# MD.net
KiCad netlist of a schematic drawn in EAGLE
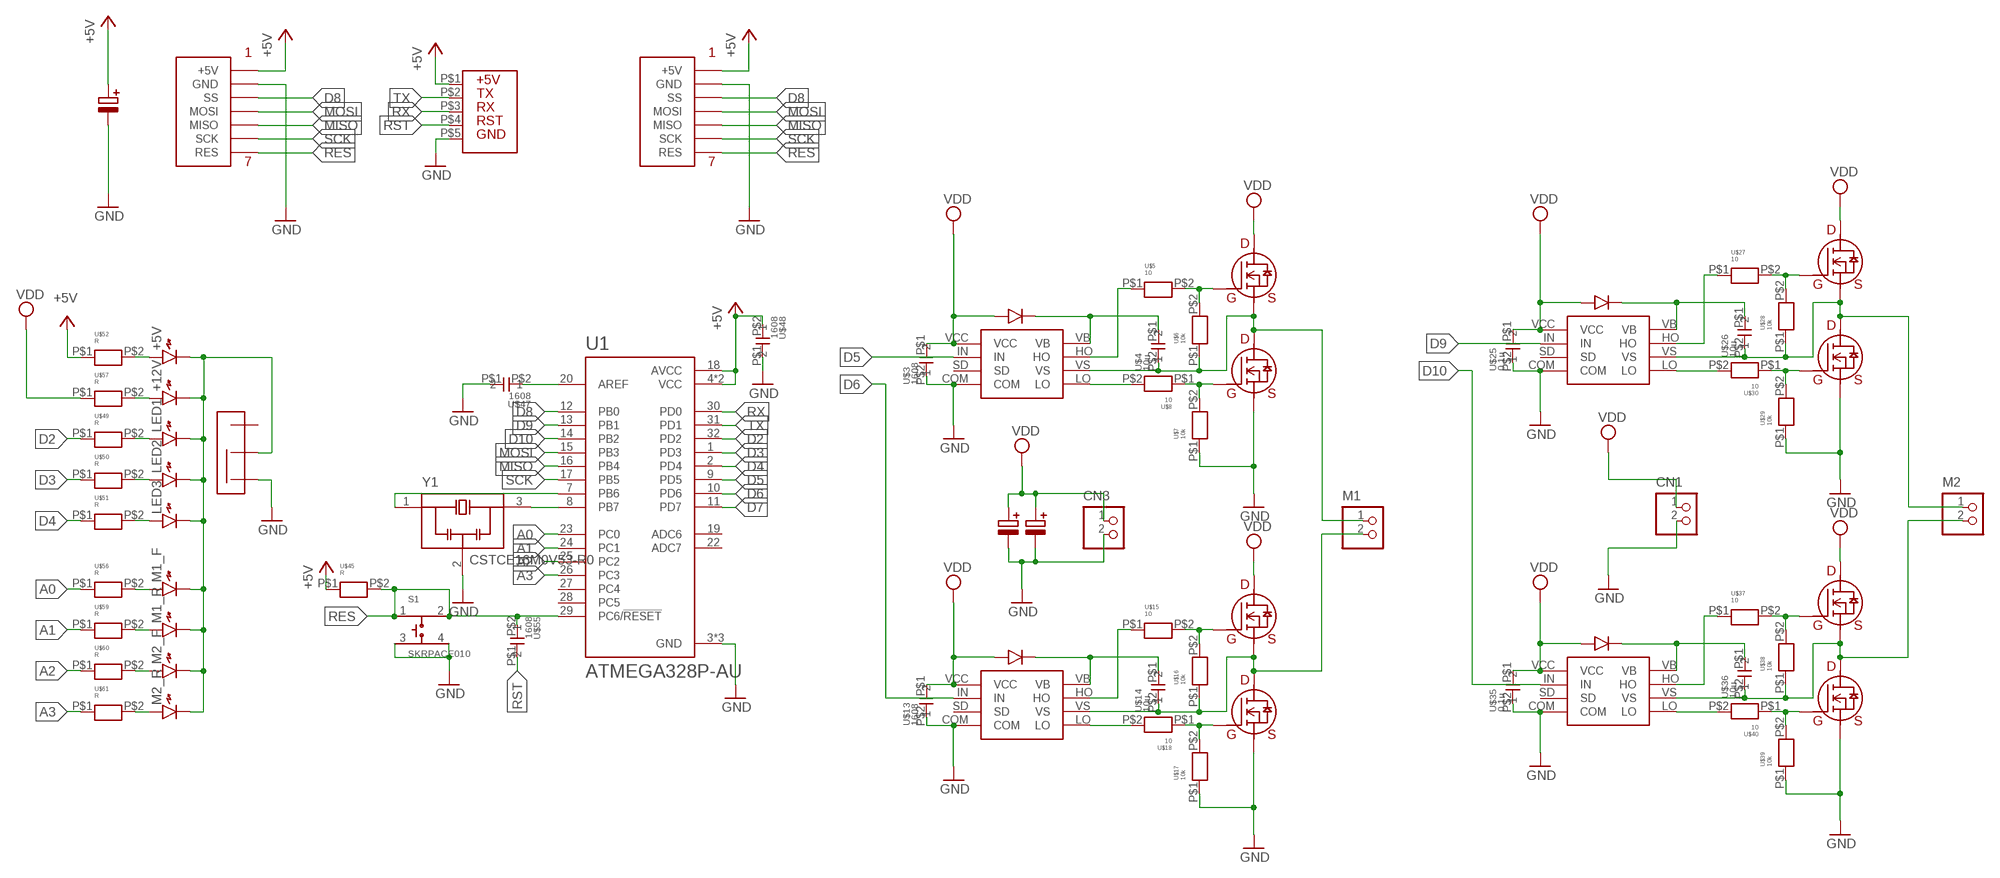
[diagram p0: schematic, sheet 1]

(export (version "E")
  (design (tool "Eeschema 10.0.6"))
  (components
    (comp (ref "+5V")
      (value "LED1608")
      (footprint "eagle-import:LED1608")
      (libsource (lib "eagle-import") (part "LED1608"))
    )
    (comp (ref "+12V")
      (value "LED1608")
      (footprint "eagle-import:LED1608")
      (libsource (lib "eagle-import") (part "LED1608"))
    )
    (comp (ref "CN1")
      (value "B2B-XH-A")
      (footprint "eagle-import:B2B-XH-A")
      (libsource (lib "eagle-import") (part "B2B-XH-A"))
    )
    (comp (ref "CN3")
      (value "B2B-XH-A")
      (footprint "eagle-import:B2B-XH-A")
      (libsource (lib "eagle-import") (part "B2B-XH-A"))
    )
    (comp (ref "LED1")
      (value "LED1608")
      (footprint "eagle-import:LED1608")
      (libsource (lib "eagle-import") (part "LED1608"))
    )
    (comp (ref "LED2")
      (value "LED1608")
      (footprint "eagle-import:LED1608")
      (libsource (lib "eagle-import") (part "LED1608"))
    )
    (comp (ref "LED3")
      (value "LED1608")
      (footprint "eagle-import:LED1608")
      (libsource (lib "eagle-import") (part "LED1608"))
    )
    (comp (ref "M1")
      (value "S2B-XH-A")
      (footprint "eagle-import:S2B-XH-A")
      (libsource (lib "eagle-import") (part "S2B-XH-A"))
    )
    (comp (ref "M1_F")
      (value "LED1608")
      (footprint "eagle-import:LED1608")
      (libsource (lib "eagle-import") (part "LED1608"))
    )
    (comp (ref "M1_R")
      (value "LED1608")
      (footprint "eagle-import:LED1608")
      (libsource (lib "eagle-import") (part "LED1608"))
    )
    (comp (ref "M2")
      (value "S2B-XH-A")
      (footprint "eagle-import:S2B-XH-A")
      (libsource (lib "eagle-import") (part "S2B-XH-A"))
    )
    (comp (ref "M2_F")
      (value "LED1608")
      (footprint "eagle-import:LED1608")
      (libsource (lib "eagle-import") (part "LED1608"))
    )
    (comp (ref "M2_R")
      (value "LED1608")
      (footprint "eagle-import:LED1608")
      (libsource (lib "eagle-import") (part "LED1608"))
    )
    (comp (ref "S1")
      (value "SKRPACE010")
      (footprint "eagle-import:SW_SKRPACE010")
      (fields (field (name "MF") "ALPS"))
      (libsource (lib "eagle-import") (part "SKRPACE010"))
    )
    (comp (ref "U$1")
      (value "IR2302")
      (footprint "eagle-import:IR2302")
      (libsource (lib "eagle-import") (part "IR2302"))
    )
    (comp (ref "U$2")
      (value "1N4148")
      (footprint "eagle-import:1N4148")
      (libsource (lib "eagle-import") (part "1N4148"))
    )
    (comp (ref "U$3")
      (value "1608")
      (footprint "eagle-import:CON")
      (libsource (lib "eagle-import") (part "1608"))
    )
    (comp (ref "U$4")
      (value "10u")
      (footprint "eagle-import:CON")
      (libsource (lib "eagle-import") (part "1608"))
    )
    (comp (ref "U$5")
      (value "10")
      (footprint "eagle-import:1608")
      (libsource (lib "eagle-import") (part "R"))
    )
    (comp (ref "U$6")
      (value "10k")
      (footprint "eagle-import:1608")
      (libsource (lib "eagle-import") (part "R"))
    )
    (comp (ref "U$7")
      (value "10k")
      (footprint "eagle-import:1608")
      (libsource (lib "eagle-import") (part "R"))
    )
    (comp (ref "U$8")
      (value "10")
      (footprint "eagle-import:1608")
      (libsource (lib "eagle-import") (part "R"))
    )
    (comp (ref "U$9")
      (value "TK8S06K3L")
      (footprint "eagle-import:TK8S06K3L")
      (libsource (lib "eagle-import") (part "TK8S06K3L"))
    )
    (comp (ref "U$10")
      (value "TK8S06K3L")
      (footprint "eagle-import:TK8S06K3L")
      (libsource (lib "eagle-import") (part "TK8S06K3L"))
    )
    (comp (ref "U$11")
      (value "IR2302")
      (footprint "eagle-import:IR2302")
      (libsource (lib "eagle-import") (part "IR2302"))
    )
    (comp (ref "U$12")
      (value "1N4148")
      (footprint "eagle-import:1N4148")
      (libsource (lib "eagle-import") (part "1N4148"))
    )
    (comp (ref "U$13")
      (value "1608")
      (footprint "eagle-import:CON")
      (libsource (lib "eagle-import") (part "1608"))
    )
    (comp (ref "U$14")
      (value "10u")
      (footprint "eagle-import:CON")
      (libsource (lib "eagle-import") (part "1608"))
    )
    (comp (ref "U$15")
      (value "10")
      (footprint "eagle-import:1608")
      (libsource (lib "eagle-import") (part "R"))
    )
    (comp (ref "U$16")
      (value "10k")
      (footprint "eagle-import:1608")
      (libsource (lib "eagle-import") (part "R"))
    )
    (comp (ref "U$17")
      (value "10k")
      (footprint "eagle-import:1608")
      (libsource (lib "eagle-import") (part "R"))
    )
    (comp (ref "U$18")
      (value "10")
      (footprint "eagle-import:1608")
      (libsource (lib "eagle-import") (part "R"))
    )
    (comp (ref "U$19")
      (value "TK8S06K3L")
      (footprint "eagle-import:TK8S06K3L")
      (libsource (lib "eagle-import") (part "TK8S06K3L"))
    )
    (comp (ref "U$20")
      (value "TK8S06K3L")
      (footprint "eagle-import:TK8S06K3L")
      (libsource (lib "eagle-import") (part "TK8S06K3L"))
    )
    (comp (ref "U$21")
      (value "25V100")
      (footprint "eagle-import:25V100")
      (libsource (lib "eagle-import") (part "25V100"))
    )
    (comp (ref "U$22")
      (value "25V100")
      (footprint "eagle-import:25V100")
      (libsource (lib "eagle-import") (part "25V100"))
    )
    (comp (ref "U$23")
      (value "IR2302")
      (footprint "eagle-import:IR2302")
      (libsource (lib "eagle-import") (part "IR2302"))
    )
    (comp (ref "U$24")
      (value "1N4148")
      (footprint "eagle-import:1N4148")
      (libsource (lib "eagle-import") (part "1N4148"))
    )
    (comp (ref "U$25")
      (value "0.1u")
      (footprint "eagle-import:CON")
      (libsource (lib "eagle-import") (part "1608"))
    )
    (comp (ref "U$26")
      (value "10u")
      (footprint "eagle-import:CON")
      (libsource (lib "eagle-import") (part "1608"))
    )
    (comp (ref "U$27")
      (value "10")
      (footprint "eagle-import:1608")
      (libsource (lib "eagle-import") (part "R"))
    )
    (comp (ref "U$28")
      (value "10k")
      (footprint "eagle-import:1608")
      (libsource (lib "eagle-import") (part "R"))
    )
    (comp (ref "U$29")
      (value "10k")
      (footprint "eagle-import:1608")
      (libsource (lib "eagle-import") (part "R"))
    )
    (comp (ref "U$30")
      (value "10")
      (footprint "eagle-import:1608")
      (libsource (lib "eagle-import") (part "R"))
    )
    (comp (ref "U$31")
      (value "TK8S06K3L")
      (footprint "eagle-import:TK8S06K3L")
      (libsource (lib "eagle-import") (part "TK8S06K3L"))
    )
    (comp (ref "U$32")
      (value "TK8S06K3L")
      (footprint "eagle-import:TK8S06K3L")
      (libsource (lib "eagle-import") (part "TK8S06K3L"))
    )
    (comp (ref "U$33")
      (value "IR2302")
      (footprint "eagle-import:IR2302")
      (libsource (lib "eagle-import") (part "IR2302"))
    )
    (comp (ref "U$34")
      (value "1N4148")
      (footprint "eagle-import:1N4148")
      (libsource (lib "eagle-import") (part "1N4148"))
    )
    (comp (ref "U$35")
      (value "0.1u")
      (footprint "eagle-import:CON")
      (libsource (lib "eagle-import") (part "1608"))
    )
    (comp (ref "U$36")
      (value "10u")
      (footprint "eagle-import:CON")
      (libsource (lib "eagle-import") (part "1608"))
    )
    (comp (ref "U$37")
      (value "10")
      (footprint "eagle-import:1608")
      (libsource (lib "eagle-import") (part "R"))
    )
    (comp (ref "U$38")
      (value "10k")
      (footprint "eagle-import:1608")
      (libsource (lib "eagle-import") (part "R"))
    )
    (comp (ref "U$39")
      (value "10k")
      (footprint "eagle-import:1608")
      (libsource (lib "eagle-import") (part "R"))
    )
    (comp (ref "U$40")
      (value "10")
      (footprint "eagle-import:1608")
      (libsource (lib "eagle-import") (part "R"))
    )
    (comp (ref "U$41")
      (value "TK8S06K3L")
      (footprint "eagle-import:TK8S06K3L")
      (libsource (lib "eagle-import") (part "TK8S06K3L"))
    )
    (comp (ref "U$42")
      (value "TK8S06K3L")
      (footprint "eagle-import:TK8S06K3L")
      (libsource (lib "eagle-import") (part "TK8S06K3L"))
    )
    (comp (ref "U$45")
      (value "R")
      (footprint "eagle-import:1608")
      (libsource (lib "eagle-import") (part "R"))
    )
    (comp (ref "U$46")
      (value "SPI")
      (footprint "eagle-import:SPI")
      (libsource (lib "eagle-import") (part "SPI"))
    )
    (comp (ref "U$47")
      (value "1608")
      (footprint "eagle-import:CON")
      (libsource (lib "eagle-import") (part "1608"))
    )
    (comp (ref "U$48")
      (value "1608")
      (footprint "eagle-import:CON")
      (libsource (lib "eagle-import") (part "1608"))
    )
    (comp (ref "U$49")
      (value "R")
      (footprint "eagle-import:1608")
      (libsource (lib "eagle-import") (part "R"))
    )
    (comp (ref "U$50")
      (value "R")
      (footprint "eagle-import:1608")
      (libsource (lib "eagle-import") (part "R"))
    )
    (comp (ref "U$51")
      (value "R")
      (footprint "eagle-import:1608")
      (libsource (lib "eagle-import") (part "R"))
    )
    (comp (ref "U$52")
      (value "R")
      (footprint "eagle-import:1608")
      (libsource (lib "eagle-import") (part "R"))
    )
    (comp (ref "U$53")
      (value "SSW")
      (footprint "eagle-import:SSW")
      (libsource (lib "eagle-import") (part "SSW"))
    )
    (comp (ref "U$54")
      (value "SI")
      (footprint "eagle-import:SI")
      (libsource (lib "eagle-import") (part "SI"))
    )
    (comp (ref "U$55")
      (value "1608")
      (footprint "eagle-import:CON")
      (libsource (lib "eagle-import") (part "1608"))
    )
    (comp (ref "U$56")
      (value "R")
      (footprint "eagle-import:1608")
      (libsource (lib "eagle-import") (part "R"))
    )
    (comp (ref "U$57")
      (value "R")
      (footprint "eagle-import:1608")
      (libsource (lib "eagle-import") (part "R"))
    )
    (comp (ref "U$58")
      (value "25V100")
      (footprint "eagle-import:25V100")
      (libsource (lib "eagle-import") (part "25V100"))
    )
    (comp (ref "U$59")
      (value "R")
      (footprint "eagle-import:1608")
      (libsource (lib "eagle-import") (part "R"))
    )
    (comp (ref "U$60")
      (value "R")
      (footprint "eagle-import:1608")
      (libsource (lib "eagle-import") (part "R"))
    )
    (comp (ref "U$61")
      (value "R")
      (footprint "eagle-import:1608")
      (libsource (lib "eagle-import") (part "R"))
    )
    (comp (ref "U$62")
      (value "SPI")
      (footprint "eagle-import:SPI")
      (libsource (lib "eagle-import") (part "SPI"))
    )
    (comp (ref "U1")
      (value "ATMEGA328P-AU")
      (footprint "eagle-import:QFP80P900X900X120-32N")
      (fields (field (name "MF") "Microchip Technology"))
      (libsource (lib "eagle-import") (part "ATMEGA328P-AU"))
    )
    (comp (ref "Y1")
      (value "CSTCE16M0V53-R0")
      (footprint "eagle-import:OSC_CSTCE16M0V53-R0")
      (fields (field (name "MANUFACTURER") "Murata"))
      (libsource (lib "eagle-import") (part "CSTCE16M0V53-R0"))
    )
  )
  (nets
    (net (code "1") (name "+5V") (class "Default")
      (node (ref "U$45") (pin "P$1") (pinfunction "P$1_P$1") (pintype "bidirectional"))
      (node (ref "U$46") (pin "P$1") (pinfunction "+5V_P$1") (pintype "bidirectional"))
      (node (ref "U$48") (pin "P$2") (pinfunction "2_P$2") (pintype "bidirectional"))
      (node (ref "U$52") (pin "P$1") (pinfunction "P$1_P$1") (pintype "bidirectional"))
      (node (ref "U$54") (pin "P$1") (pinfunction "P$1_P$1") (pintype "bidirectional"))
      (node (ref "U$58") (pin "P$1") (pinfunction "P$1_P$1") (pintype "bidirectional"))
      (node (ref "U$62") (pin "P$1") (pinfunction "+5V_P$1") (pintype "bidirectional"))
      (node (ref "U1") (pin "18") (pinfunction "AVCC_18") (pintype "power_in"))
      (node (ref "U1") (pin "4") (pinfunction "VCC_4") (pintype "power_in"))
      (node (ref "U1") (pin "6") (pinfunction "VCC_6") (pintype "power_in"))
    )
    (net (code "2") (name "A0") (class "Default")
      (node (ref "U$56") (pin "P$1") (pinfunction "P$1_P$1") (pintype "bidirectional"))
      (node (ref "U1") (pin "23") (pinfunction "PC0_23") (pintype "bidirectional"))
    )
    (net (code "3") (name "A1") (class "Default")
      (node (ref "U$59") (pin "P$1") (pinfunction "P$1_P$1") (pintype "bidirectional"))
      (node (ref "U1") (pin "24") (pinfunction "PC1_24") (pintype "bidirectional"))
    )
    (net (code "4") (name "A2") (class "Default")
      (node (ref "U$60") (pin "P$1") (pinfunction "P$1_P$1") (pintype "bidirectional"))
      (node (ref "U1") (pin "25") (pinfunction "PC2_25") (pintype "bidirectional"))
    )
    (net (code "5") (name "A3") (class "Default")
      (node (ref "U$61") (pin "P$1") (pinfunction "P$1_P$1") (pintype "bidirectional"))
      (node (ref "U1") (pin "26") (pinfunction "PC3_26") (pintype "bidirectional"))
    )
    (net (code "6") (name "D2") (class "Default")
      (node (ref "U$49") (pin "P$1") (pinfunction "P$1_P$1") (pintype "bidirectional"))
      (node (ref "U1") (pin "32") (pinfunction "PD2_32") (pintype "bidirectional"))
    )
    (net (code "7") (name "D3") (class "Default")
      (node (ref "U$50") (pin "P$1") (pinfunction "P$1_P$1") (pintype "bidirectional"))
      (node (ref "U1") (pin "1") (pinfunction "PD3_1") (pintype "bidirectional"))
    )
    (net (code "8") (name "D4") (class "Default")
      (node (ref "U$51") (pin "P$1") (pinfunction "P$1_P$1") (pintype "bidirectional"))
      (node (ref "U1") (pin "2") (pinfunction "PD4_2") (pintype "bidirectional"))
    )
    (net (code "9") (name "D5") (class "Default")
      (node (ref "U$1") (pin "IN") (pinfunction "IN_IN") (pintype "bidirectional"))
      (node (ref "U1") (pin "9") (pinfunction "PD5_9") (pintype "bidirectional"))
    )
    (net (code "10") (name "D6") (class "Default")
      (node (ref "U$11") (pin "IN") (pinfunction "IN_IN") (pintype "bidirectional"))
      (node (ref "U1") (pin "10") (pinfunction "PD6_10") (pintype "bidirectional"))
    )
    (net (code "11") (name "D7") (class "Default")
      (node (ref "U1") (pin "11") (pinfunction "PD7_11") (pintype "bidirectional"))
    )
    (net (code "12") (name "D8") (class "Default")
      (node (ref "U$46") (pin "P$3") (pinfunction "SS_P$3") (pintype "bidirectional"))
      (node (ref "U$62") (pin "P$3") (pinfunction "SS_P$3") (pintype "bidirectional"))
      (node (ref "U1") (pin "12") (pinfunction "PB0_12") (pintype "bidirectional"))
    )
    (net (code "13") (name "D9") (class "Default")
      (node (ref "U$23") (pin "IN") (pinfunction "IN_IN") (pintype "bidirectional"))
      (node (ref "U1") (pin "13") (pinfunction "PB1_13") (pintype "bidirectional"))
    )
    (net (code "14") (name "D10") (class "Default")
      (node (ref "U$33") (pin "IN") (pinfunction "IN_IN") (pintype "bidirectional"))
      (node (ref "U1") (pin "14") (pinfunction "PB2_14") (pintype "bidirectional"))
    )
    (net (code "15") (name "GND") (class "Default")
      (node (ref "CN1") (pin "2") (pinfunction "2_2") (pintype "passive"))
      (node (ref "CN3") (pin "2") (pinfunction "2_2") (pintype "passive"))
      (node (ref "S1") (pin "3") (pinfunction "3_3") (pintype "bidirectional"))
      (node (ref "S1") (pin "4") (pinfunction "4_4") (pintype "bidirectional"))
      (node (ref "U$1") (pin "COM") (pinfunction "COM_COM") (pintype "bidirectional"))
      (node (ref "U$10") (pin "S") (pinfunction "S_S") (pintype "bidirectional"))
      (node (ref "U$11") (pin "COM") (pinfunction "COM_COM") (pintype "bidirectional"))
      (node (ref "U$13") (pin "P$2") (pinfunction "2_P$2") (pintype "bidirectional"))
      (node (ref "U$17") (pin "P$1") (pinfunction "P$1_P$1") (pintype "bidirectional"))
      (node (ref "U$20") (pin "S") (pinfunction "S_S") (pintype "bidirectional"))
      (node (ref "U$21") (pin "P$2") (pinfunction "P$2_P$2") (pintype "bidirectional"))
      (node (ref "U$22") (pin "P$2") (pinfunction "P$2_P$2") (pintype "bidirectional"))
      (node (ref "U$23") (pin "COM") (pinfunction "COM_COM") (pintype "bidirectional"))
      (node (ref "U$25") (pin "P$2") (pinfunction "2_P$2") (pintype "bidirectional"))
      (node (ref "U$29") (pin "P$1") (pinfunction "P$1_P$1") (pintype "bidirectional"))
      (node (ref "U$3") (pin "P$2") (pinfunction "2_P$2") (pintype "bidirectional"))
      (node (ref "U$32") (pin "S") (pinfunction "S_S") (pintype "bidirectional"))
      (node (ref "U$33") (pin "COM") (pinfunction "COM_COM") (pintype "bidirectional"))
      (node (ref "U$35") (pin "P$2") (pinfunction "2_P$2") (pintype "bidirectional"))
      (node (ref "U$39") (pin "P$1") (pinfunction "P$1_P$1") (pintype "bidirectional"))
      (node (ref "U$42") (pin "S") (pinfunction "S_S") (pintype "bidirectional"))
      (node (ref "U$46") (pin "P$2") (pinfunction "GND_P$2") (pintype "bidirectional"))
      (node (ref "U$47") (pin "P$1") (pinfunction "1_P$1") (pintype "bidirectional"))
      (node (ref "U$48") (pin "P$1") (pinfunction "1_P$1") (pintype "bidirectional"))
      (node (ref "U$53") (pin "P$1") (pinfunction "P$1_P$1") (pintype "bidirectional"))
      (node (ref "U$54") (pin "P$5") (pinfunction "P$5_P$5") (pintype "bidirectional"))
      (node (ref "U$58") (pin "P$2") (pinfunction "P$2_P$2") (pintype "bidirectional"))
      (node (ref "U$62") (pin "P$2") (pinfunction "GND_P$2") (pintype "bidirectional"))
      (node (ref "U$7") (pin "P$1") (pinfunction "P$1_P$1") (pintype "bidirectional"))
      (node (ref "U1") (pin "21") (pinfunction "GND_21") (pintype "power_in"))
      (node (ref "U1") (pin "3") (pinfunction "GND_3") (pintype "power_in"))
      (node (ref "U1") (pin "5") (pinfunction "GND_5") (pintype "power_in"))
      (node (ref "Y1") (pin "2") (pinfunction "GND_2") (pintype "power_in"))
    )
    (net (code "16") (name "MISO") (class "Default")
      (node (ref "U$46") (pin "P$5") (pinfunction "MISO_P$5") (pintype "bidirectional"))
      (node (ref "U$62") (pin "P$5") (pinfunction "MISO_P$5") (pintype "bidirectional"))
      (node (ref "U1") (pin "16") (pinfunction "PB4_16") (pintype "bidirectional"))
    )
    (net (code "17") (name "MOSI") (class "Default")
      (node (ref "U$46") (pin "P$4") (pinfunction "MOSI_P$4") (pintype "bidirectional"))
      (node (ref "U$62") (pin "P$4") (pinfunction "MOSI_P$4") (pintype "bidirectional"))
      (node (ref "U1") (pin "15") (pinfunction "PB3_15") (pintype "bidirectional"))
    )
    (net (code "18") (name "Net-(+5V-PadA)") (class "Default")
      (node (ref "+5V") (pin "A") (pinfunction "A_A") (pintype "passive"))
      (node (ref "U$52") (pin "P$2") (pinfunction "P$2_P$2") (pintype "bidirectional"))
    )
    (net (code "19") (name "Net-(+12V-PadA)") (class "Default")
      (node (ref "+12V") (pin "A") (pinfunction "A_A") (pintype "passive"))
      (node (ref "U$57") (pin "P$2") (pinfunction "P$2_P$2") (pintype "bidirectional"))
    )
    (net (code "20") (name "Net-(LED1-PadA)") (class "Default")
      (node (ref "LED1") (pin "A") (pinfunction "A_A") (pintype "passive"))
      (node (ref "U$49") (pin "P$2") (pinfunction "P$2_P$2") (pintype "bidirectional"))
    )
    (net (code "21") (name "Net-(LED2-PadA)") (class "Default")
      (node (ref "LED2") (pin "A") (pinfunction "A_A") (pintype "passive"))
      (node (ref "U$50") (pin "P$2") (pinfunction "P$2_P$2") (pintype "bidirectional"))
    )
    (net (code "22") (name "Net-(LED3-PadA)") (class "Default")
      (node (ref "LED3") (pin "A") (pinfunction "A_A") (pintype "passive"))
      (node (ref "U$51") (pin "P$2") (pinfunction "P$2_P$2") (pintype "bidirectional"))
    )
    (net (code "23") (name "Net-(M1_F-PadA)") (class "Default")
      (node (ref "M1_F") (pin "A") (pinfunction "A_A") (pintype "passive"))
      (node (ref "U$56") (pin "P$2") (pinfunction "P$2_P$2") (pintype "bidirectional"))
    )
    (net (code "24") (name "Net-(M1_R-PadA)") (class "Default")
      (node (ref "M1_R") (pin "A") (pinfunction "A_A") (pintype "passive"))
      (node (ref "U$59") (pin "P$2") (pinfunction "P$2_P$2") (pintype "bidirectional"))
    )
    (net (code "25") (name "Net-(M2_F-PadA)") (class "Default")
      (node (ref "M2_F") (pin "A") (pinfunction "A_A") (pintype "passive"))
      (node (ref "U$60") (pin "P$2") (pinfunction "P$2_P$2") (pintype "bidirectional"))
    )
    (net (code "26") (name "Net-(M2_R-PadA)") (class "Default")
      (node (ref "M2_R") (pin "A") (pinfunction "A_A") (pintype "passive"))
      (node (ref "U$61") (pin "P$2") (pinfunction "P$2_P$2") (pintype "bidirectional"))
    )
    (net (code "27") (name "Net-(U$1-PadHO)") (class "Default")
      (node (ref "U$1") (pin "HO") (pinfunction "HO_HO") (pintype "bidirectional"))
      (node (ref "U$5") (pin "P$1") (pinfunction "P$1_P$1") (pintype "bidirectional"))
    )
    (net (code "28") (name "Net-(U$1-PadLO)") (class "Default")
      (node (ref "U$1") (pin "LO") (pinfunction "LO_LO") (pintype "bidirectional"))
      (node (ref "U$8") (pin "P$2") (pinfunction "P$2_P$2") (pintype "bidirectional"))
    )
    (net (code "29") (name "Net-(U$4-1)") (class "Default")
      (node (ref "U$1") (pin "VB") (pinfunction "VB_VB") (pintype "bidirectional"))
      (node (ref "U$2") (pin "P$2") (pinfunction "P$2_P$2") (pintype "bidirectional"))
      (node (ref "U$4") (pin "P$1") (pinfunction "1_P$1") (pintype "bidirectional"))
    )
    (net (code "30") (name "Net-(U$4-2)") (class "Default")
      (node (ref "M1") (pin "1") (pinfunction "1_1") (pintype "passive"))
      (node (ref "U$1") (pin "VS") (pinfunction "VS_VS") (pintype "bidirectional"))
      (node (ref "U$10") (pin "D") (pinfunction "D_D") (pintype "bidirectional"))
      (node (ref "U$4") (pin "P$2") (pinfunction "2_P$2") (pintype "bidirectional"))
      (node (ref "U$6") (pin "P$1") (pinfunction "P$1_P$1") (pintype "bidirectional"))
      (node (ref "U$9") (pin "S") (pinfunction "S_S") (pintype "bidirectional"))
    )
    (net (code "31") (name "Net-(U$5-PadP$2)") (class "Default")
      (node (ref "U$5") (pin "P$2") (pinfunction "P$2_P$2") (pintype "bidirectional"))
      (node (ref "U$6") (pin "P$2") (pinfunction "P$2_P$2") (pintype "bidirectional"))
      (node (ref "U$9") (pin "G") (pinfunction "G_G") (pintype "bidirectional"))
    )
    (net (code "32") (name "Net-(U$10-PadG)") (class "Default")
      (node (ref "U$10") (pin "G") (pinfunction "G_G") (pintype "bidirectional"))
      (node (ref "U$7") (pin "P$2") (pinfunction "P$2_P$2") (pintype "bidirectional"))
      (node (ref "U$8") (pin "P$1") (pinfunction "P$1_P$1") (pintype "bidirectional"))
    )
    (net (code "33") (name "Net-(U$11-PadHO)") (class "Default")
      (node (ref "U$11") (pin "HO") (pinfunction "HO_HO") (pintype "bidirectional"))
      (node (ref "U$15") (pin "P$1") (pinfunction "P$1_P$1") (pintype "bidirectional"))
    )
    (net (code "34") (name "Net-(U$11-PadLO)") (class "Default")
      (node (ref "U$11") (pin "LO") (pinfunction "LO_LO") (pintype "bidirectional"))
      (node (ref "U$18") (pin "P$2") (pinfunction "P$2_P$2") (pintype "bidirectional"))
    )
    (net (code "35") (name "Net-(U$14-1)") (class "Default")
      (node (ref "U$11") (pin "VB") (pinfunction "VB_VB") (pintype "bidirectional"))
      (node (ref "U$12") (pin "P$2") (pinfunction "P$2_P$2") (pintype "bidirectional"))
      (node (ref "U$14") (pin "P$1") (pinfunction "1_P$1") (pintype "bidirectional"))
    )
    (net (code "36") (name "Net-(U$14-2)") (class "Default")
      (node (ref "M1") (pin "2") (pinfunction "2_2") (pintype "passive"))
      (node (ref "U$11") (pin "VS") (pinfunction "VS_VS") (pintype "bidirectional"))
      (node (ref "U$14") (pin "P$2") (pinfunction "2_P$2") (pintype "bidirectional"))
      (node (ref "U$16") (pin "P$1") (pinfunction "P$1_P$1") (pintype "bidirectional"))
      (node (ref "U$19") (pin "S") (pinfunction "S_S") (pintype "bidirectional"))
      (node (ref "U$20") (pin "D") (pinfunction "D_D") (pintype "bidirectional"))
    )
    (net (code "37") (name "Net-(U$15-PadP$2)") (class "Default")
      (node (ref "U$15") (pin "P$2") (pinfunction "P$2_P$2") (pintype "bidirectional"))
      (node (ref "U$16") (pin "P$2") (pinfunction "P$2_P$2") (pintype "bidirectional"))
      (node (ref "U$19") (pin "G") (pinfunction "G_G") (pintype "bidirectional"))
    )
    (net (code "38") (name "Net-(U$17-PadP$2)") (class "Default")
      (node (ref "U$17") (pin "P$2") (pinfunction "P$2_P$2") (pintype "bidirectional"))
      (node (ref "U$18") (pin "P$1") (pinfunction "P$1_P$1") (pintype "bidirectional"))
      (node (ref "U$20") (pin "G") (pinfunction "G_G") (pintype "bidirectional"))
    )
    (net (code "39") (name "Net-(U$23-PadHO)") (class "Default")
      (node (ref "U$23") (pin "HO") (pinfunction "HO_HO") (pintype "bidirectional"))
      (node (ref "U$27") (pin "P$1") (pinfunction "P$1_P$1") (pintype "bidirectional"))
    )
    (net (code "40") (name "Net-(U$23-PadLO)") (class "Default")
      (node (ref "U$23") (pin "LO") (pinfunction "LO_LO") (pintype "bidirectional"))
      (node (ref "U$30") (pin "P$2") (pinfunction "P$2_P$2") (pintype "bidirectional"))
    )
    (net (code "41") (name "Net-(U$26-1)") (class "Default")
      (node (ref "U$23") (pin "VB") (pinfunction "VB_VB") (pintype "bidirectional"))
      (node (ref "U$24") (pin "P$2") (pinfunction "P$2_P$2") (pintype "bidirectional"))
      (node (ref "U$26") (pin "P$1") (pinfunction "1_P$1") (pintype "bidirectional"))
    )
    (net (code "42") (name "Net-(U$26-2)") (class "Default")
      (node (ref "M2") (pin "1") (pinfunction "1_1") (pintype "passive"))
      (node (ref "U$23") (pin "VS") (pinfunction "VS_VS") (pintype "bidirectional"))
      (node (ref "U$26") (pin "P$2") (pinfunction "2_P$2") (pintype "bidirectional"))
      (node (ref "U$28") (pin "P$1") (pinfunction "P$1_P$1") (pintype "bidirectional"))
      (node (ref "U$31") (pin "S") (pinfunction "S_S") (pintype "bidirectional"))
      (node (ref "U$32") (pin "D") (pinfunction "D_D") (pintype "bidirectional"))
    )
    (net (code "43") (name "Net-(U$27-PadP$2)") (class "Default")
      (node (ref "U$27") (pin "P$2") (pinfunction "P$2_P$2") (pintype "bidirectional"))
      (node (ref "U$28") (pin "P$2") (pinfunction "P$2_P$2") (pintype "bidirectional"))
      (node (ref "U$31") (pin "G") (pinfunction "G_G") (pintype "bidirectional"))
    )
    (net (code "44") (name "Net-(U$29-PadP$2)") (class "Default")
      (node (ref "U$29") (pin "P$2") (pinfunction "P$2_P$2") (pintype "bidirectional"))
      (node (ref "U$30") (pin "P$1") (pinfunction "P$1_P$1") (pintype "bidirectional"))
      (node (ref "U$32") (pin "G") (pinfunction "G_G") (pintype "bidirectional"))
    )
    (net (code "45") (name "Net-(U$33-PadHO)") (class "Default")
      (node (ref "U$33") (pin "HO") (pinfunction "HO_HO") (pintype "bidirectional"))
      (node (ref "U$37") (pin "P$1") (pinfunction "P$1_P$1") (pintype "bidirectional"))
    )
    (net (code "46") (name "Net-(U$33-PadLO)") (class "Default")
      (node (ref "U$33") (pin "LO") (pinfunction "LO_LO") (pintype "bidirectional"))
      (node (ref "U$40") (pin "P$2") (pinfunction "P$2_P$2") (pintype "bidirectional"))
    )
    (net (code "47") (name "Net-(U$36-1)") (class "Default")
      (node (ref "U$33") (pin "VB") (pinfunction "VB_VB") (pintype "bidirectional"))
      (node (ref "U$34") (pin "P$2") (pinfunction "P$2_P$2") (pintype "bidirectional"))
      (node (ref "U$36") (pin "P$1") (pinfunction "1_P$1") (pintype "bidirectional"))
    )
    (net (code "48") (name "Net-(U$36-2)") (class "Default")
      (node (ref "M2") (pin "2") (pinfunction "2_2") (pintype "passive"))
      (node (ref "U$33") (pin "VS") (pinfunction "VS_VS") (pintype "bidirectional"))
      (node (ref "U$36") (pin "P$2") (pinfunction "2_P$2") (pintype "bidirectional"))
      (node (ref "U$38") (pin "P$1") (pinfunction "P$1_P$1") (pintype "bidirectional"))
      (node (ref "U$41") (pin "S") (pinfunction "S_S") (pintype "bidirectional"))
      (node (ref "U$42") (pin "D") (pinfunction "D_D") (pintype "bidirectional"))
    )
    (net (code "49") (name "Net-(U$37-PadP$2)") (class "Default")
      (node (ref "U$37") (pin "P$2") (pinfunction "P$2_P$2") (pintype "bidirectional"))
      (node (ref "U$38") (pin "P$2") (pinfunction "P$2_P$2") (pintype "bidirectional"))
      (node (ref "U$41") (pin "G") (pinfunction "G_G") (pintype "bidirectional"))
    )
    (net (code "50") (name "Net-(U$39-PadP$2)") (class "Default")
      (node (ref "U$39") (pin "P$2") (pinfunction "P$2_P$2") (pintype "bidirectional"))
      (node (ref "U$40") (pin "P$1") (pinfunction "P$1_P$1") (pintype "bidirectional"))
      (node (ref "U$42") (pin "G") (pinfunction "G_G") (pintype "bidirectional"))
    )
    (net (code "51") (name "Net-(U$47-2)") (class "Default")
      (node (ref "U$47") (pin "P$2") (pinfunction "2_P$2") (pintype "bidirectional"))
      (node (ref "U1") (pin "20") (pinfunction "AREF_20") (pintype "input"))
    )
    (net (code "52") (name "Net-(U$53-P$2)") (class "Default")
      (node (ref "+12V") (pin "K") (pinfunction "K_K") (pintype "passive"))
      (node (ref "+5V") (pin "K") (pinfunction "K_K") (pintype "passive"))
      (node (ref "LED1") (pin "K") (pinfunction "K_K") (pintype "passive"))
      (node (ref "LED2") (pin "K") (pinfunction "K_K") (pintype "passive"))
      (node (ref "LED3") (pin "K") (pinfunction "K_K") (pintype "passive"))
      (node (ref "M1_F") (pin "K") (pinfunction "K_K") (pintype "passive"))
      (node (ref "M1_R") (pin "K") (pinfunction "K_K") (pintype "passive"))
      (node (ref "M2_F") (pin "K") (pinfunction "K_K") (pintype "passive"))
      (node (ref "M2_R") (pin "K") (pinfunction "K_K") (pintype "passive"))
      (node (ref "U$53") (pin "P$3") (pinfunction "P$2_P$3") (pintype "bidirectional"))
    )
    (net (code "53") (name "Net-(U1-PB6)") (class "Default")
      (node (ref "U1") (pin "7") (pinfunction "PB6_7") (pintype "bidirectional"))
      (node (ref "Y1") (pin "1") (pinfunction "IN_1") (pintype "input"))
    )
    (net (code "54") (name "Net-(U1-PB7)") (class "Default")
      (node (ref "U1") (pin "8") (pinfunction "PB7_8") (pintype "bidirectional"))
      (node (ref "Y1") (pin "3") (pinfunction "OUT_3") (pintype "output"))
    )
    (net (code "55") (name "RES") (class "Default")
      (node (ref "S1") (pin "1") (pinfunction "1_1") (pintype "bidirectional"))
      (node (ref "S1") (pin "2") (pinfunction "2_2") (pintype "bidirectional"))
      (node (ref "U$45") (pin "P$2") (pinfunction "P$2_P$2") (pintype "bidirectional"))
      (node (ref "U$46") (pin "P$7") (pinfunction "RES_P$7") (pintype "bidirectional"))
      (node (ref "U$55") (pin "P$2") (pinfunction "2_P$2") (pintype "bidirectional"))
      (node (ref "U$62") (pin "P$7") (pinfunction "RES_P$7") (pintype "bidirectional"))
      (node (ref "U1") (pin "29") (pinfunction "PC6/~{RESET}_29") (pintype "bidirectional"))
    )
    (net (code "56") (name "RST") (class "Default")
      (node (ref "U$54") (pin "P$4") (pinfunction "P$4_P$4") (pintype "bidirectional"))
      (node (ref "U$55") (pin "P$1") (pinfunction "1_P$1") (pintype "bidirectional"))
    )
    (net (code "57") (name "RX") (class "Default")
      (node (ref "U$54") (pin "P$3") (pinfunction "P$3_P$3") (pintype "bidirectional"))
      (node (ref "U1") (pin "30") (pinfunction "PD0_30") (pintype "bidirectional"))
    )
    (net (code "58") (name "SCK") (class "Default")
      (node (ref "U$46") (pin "P$6") (pinfunction "SCK_P$6") (pintype "bidirectional"))
      (node (ref "U$62") (pin "P$6") (pinfunction "SCK_P$6") (pintype "bidirectional"))
      (node (ref "U1") (pin "17") (pinfunction "PB5_17") (pintype "bidirectional"))
    )
    (net (code "59") (name "TX") (class "Default")
      (node (ref "U$54") (pin "P$2") (pinfunction "P$2_P$2") (pintype "bidirectional"))
      (node (ref "U1") (pin "31") (pinfunction "PD1_31") (pintype "bidirectional"))
    )
    (net (code "60") (name "VDD") (class "Default")
      (node (ref "CN1") (pin "1") (pinfunction "1_1") (pintype "passive"))
      (node (ref "CN3") (pin "1") (pinfunction "1_1") (pintype "passive"))
      (node (ref "U$1") (pin "VCC") (pinfunction "VCC_VCC") (pintype "bidirectional"))
      (node (ref "U$11") (pin "VCC") (pinfunction "VCC_VCC") (pintype "bidirectional"))
      (node (ref "U$12") (pin "P$1") (pinfunction "P$1_P$1") (pintype "bidirectional"))
      (node (ref "U$13") (pin "P$1") (pinfunction "1_P$1") (pintype "bidirectional"))
      (node (ref "U$19") (pin "D") (pinfunction "D_D") (pintype "bidirectional"))
      (node (ref "U$2") (pin "P$1") (pinfunction "P$1_P$1") (pintype "bidirectional"))
      (node (ref "U$21") (pin "P$1") (pinfunction "P$1_P$1") (pintype "bidirectional"))
      (node (ref "U$22") (pin "P$1") (pinfunction "P$1_P$1") (pintype "bidirectional"))
      (node (ref "U$23") (pin "VCC") (pinfunction "VCC_VCC") (pintype "bidirectional"))
      (node (ref "U$24") (pin "P$1") (pinfunction "P$1_P$1") (pintype "bidirectional"))
      (node (ref "U$25") (pin "P$1") (pinfunction "1_P$1") (pintype "bidirectional"))
      (node (ref "U$3") (pin "P$1") (pinfunction "1_P$1") (pintype "bidirectional"))
      (node (ref "U$31") (pin "D") (pinfunction "D_D") (pintype "bidirectional"))
      (node (ref "U$33") (pin "VCC") (pinfunction "VCC_VCC") (pintype "bidirectional"))
      (node (ref "U$34") (pin "P$1") (pinfunction "P$1_P$1") (pintype "bidirectional"))
      (node (ref "U$35") (pin "P$1") (pinfunction "1_P$1") (pintype "bidirectional"))
      (node (ref "U$41") (pin "D") (pinfunction "D_D") (pintype "bidirectional"))
      (node (ref "U$57") (pin "P$1") (pinfunction "P$1_P$1") (pintype "bidirectional"))
      (node (ref "U$9") (pin "D") (pinfunction "D_D") (pintype "bidirectional"))
    )
    (net (code "61") (name "unconnected-(U$1-PadSD)") (class "Default")
      (node (ref "U$1") (pin "SD") (pinfunction "SD_SD") (pintype "bidirectional"))
    )
    (net (code "62") (name "unconnected-(U$11-PadSD)") (class "Default")
      (node (ref "U$11") (pin "SD") (pinfunction "SD_SD") (pintype "bidirectional"))
    )
    (net (code "63") (name "unconnected-(U$23-PadSD)") (class "Default")
      (node (ref "U$23") (pin "SD") (pinfunction "SD_SD") (pintype "bidirectional"))
    )
    (net (code "64") (name "unconnected-(U$33-PadSD)") (class "Default")
      (node (ref "U$33") (pin "SD") (pinfunction "SD_SD") (pintype "bidirectional"))
    )
    (net (code "65") (name "unconnected-(U$53-P$3-PadP$2)") (class "Default")
      (node (ref "U$53") (pin "P$2") (pinfunction "P$3_P$2") (pintype "bidirectional"))
    )
    (net (code "66") (name "unconnected-(U1-ADC6-Pad19)") (class "Default")
      (node (ref "U1") (pin "19") (pinfunction "ADC6_19") (pintype "bidirectional"))
    )
    (net (code "67") (name "unconnected-(U1-ADC7-Pad22)") (class "Default")
      (node (ref "U1") (pin "22") (pinfunction "ADC7_22") (pintype "bidirectional"))
    )
    (net (code "68") (name "unconnected-(U1-PC4-Pad27)") (class "Default")
      (node (ref "U1") (pin "27") (pinfunction "PC4_27") (pintype "bidirectional"))
    )
    (net (code "69") (name "unconnected-(U1-PC5-Pad28)") (class "Default")
      (node (ref "U1") (pin "28") (pinfunction "PC5_28") (pintype "bidirectional"))
    )
  )
)
